# Version1.net
KiCad netlist of a schematic drawn in EAGLE
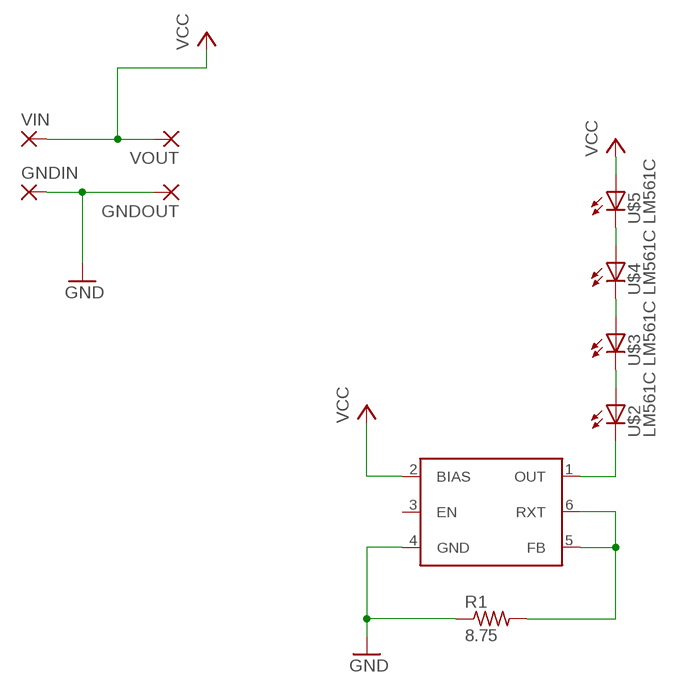
[diagram p0: schematic, sheet 1]

(export (version "E")
  (design (tool "Eeschema 10.0.6"))
  (components
    (comp (ref "GNDIN")
      (value "SMD5")
      (footprint "eagle-import:SMD2,54-5,08")
      (libsource (lib "eagle-import") (part "SMD5"))
    )
    (comp (ref "GNDOUT")
      (value "SMD5")
      (footprint "eagle-import:SMD2,54-5,08")
      (libsource (lib "eagle-import") (part "SMD5"))
    )
    (comp (ref "R1")
      (value "8.75")
      (footprint "eagle-import:R0805")
      (libsource (lib "eagle-import") (part "R-US_R0805"))
    )
    (comp (ref "U$1")
      (value "AL5802")
      (footprint "eagle-import:SOT26")
      (libsource (lib "eagle-import") (part "AL5802"))
    )
    (comp (ref "U$2")
      (value "LM561C")
      (footprint "eagle-import:LM561CPAD")
      (libsource (lib "eagle-import") (part "LM561C"))
    )
    (comp (ref "U$3")
      (value "LM561C")
      (footprint "eagle-import:LM561CPAD")
      (libsource (lib "eagle-import") (part "LM561C"))
    )
    (comp (ref "U$4")
      (value "LM561C")
      (footprint "eagle-import:LM561CPAD")
      (libsource (lib "eagle-import") (part "LM561C"))
    )
    (comp (ref "U$5")
      (value "LM561C")
      (footprint "eagle-import:LM561CPAD")
      (libsource (lib "eagle-import") (part "LM561C"))
    )
    (comp (ref "VIN")
      (value "SMD5")
      (footprint "eagle-import:SMD2,54-5,08")
      (libsource (lib "eagle-import") (part "SMD5"))
    )
    (comp (ref "VOUT")
      (value "SMD5")
      (footprint "eagle-import:SMD2,54-5,08")
      (libsource (lib "eagle-import") (part "SMD5"))
    )
  )
  (nets
    (net (code "1") (name "GND") (class "Default")
      (node (ref "GNDIN") (pin "1") (pinfunction "P_1") (pintype "passive"))
      (node (ref "GNDOUT") (pin "1") (pinfunction "P_1") (pintype "passive"))
      (node (ref "R1") (pin "1") (pinfunction "1_1") (pintype "passive"))
      (node (ref "U$1") (pin "4") (pinfunction "GND_4") (pintype "bidirectional"))
    )
    (net (code "2") (name "Net-(U$1-FB)") (class "Default")
      (node (ref "R1") (pin "2") (pinfunction "2_2") (pintype "passive"))
      (node (ref "U$1") (pin "5") (pinfunction "FB_5") (pintype "bidirectional"))
      (node (ref "U$1") (pin "6") (pinfunction "RXT_6") (pintype "bidirectional"))
    )
    (net (code "3") (name "Net-(U$1-OUT)") (class "Default")
      (node (ref "U$1") (pin "1") (pinfunction "OUT_1") (pintype "bidirectional"))
      (node (ref "U$2") (pin "CATH") (pinfunction "C_CATH") (pintype "passive"))
    )
    (net (code "4") (name "Net-(U$2-A)") (class "Default")
      (node (ref "U$2") (pin "ANODE") (pinfunction "A_ANODE") (pintype "passive"))
      (node (ref "U$3") (pin "CATH") (pinfunction "C_CATH") (pintype "passive"))
    )
    (net (code "5") (name "Net-(U$3-A)") (class "Default")
      (node (ref "U$3") (pin "ANODE") (pinfunction "A_ANODE") (pintype "passive"))
      (node (ref "U$4") (pin "CATH") (pinfunction "C_CATH") (pintype "passive"))
    )
    (net (code "6") (name "Net-(U$4-A)") (class "Default")
      (node (ref "U$4") (pin "ANODE") (pinfunction "A_ANODE") (pintype "passive"))
      (node (ref "U$5") (pin "CATH") (pinfunction "C_CATH") (pintype "passive"))
    )
    (net (code "7") (name "VCC") (class "Default")
      (node (ref "U$1") (pin "2") (pinfunction "BIAS_2") (pintype "bidirectional"))
      (node (ref "U$5") (pin "ANODE") (pinfunction "A_ANODE") (pintype "passive"))
      (node (ref "VIN") (pin "1") (pinfunction "P_1") (pintype "passive"))
      (node (ref "VOUT") (pin "1") (pinfunction "P_1") (pintype "passive"))
    )
    (net (code "8") (name "unconnected-(U$1-EN-Pad3)") (class "Default")
      (node (ref "U$1") (pin "3") (pinfunction "EN_3") (pintype "bidirectional"))
    )
  )
)
